# untitled.net
KiCad netlist of a schematic drawn in EAGLE
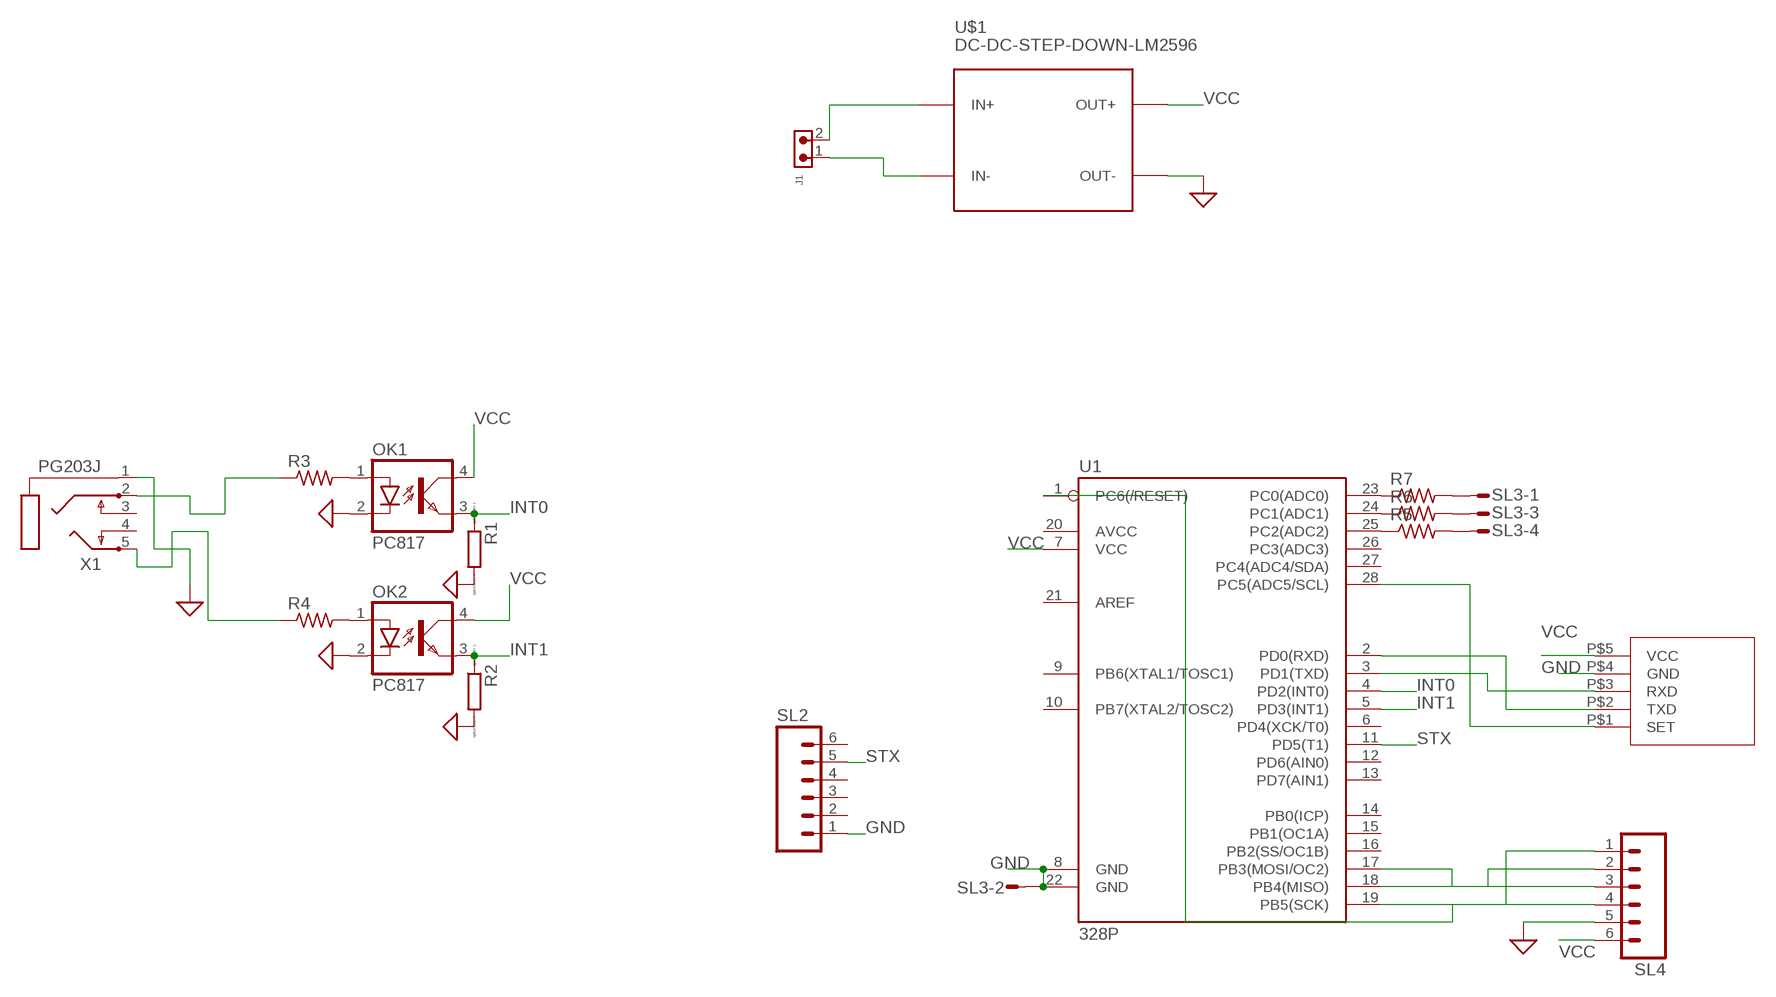
[diagram p0: schematic, sheet 1]

(export (version "E")
  (design (tool "Eeschema 10.0.6"))
  (components
    (comp (ref "J1")
      (value "691305530002")
      (footprint "eagle-import:691305530002")
      (libsource (lib "eagle-import") (part "691305530002"))
    )
    (comp (ref "OK1")
      (value "PC817")
      (footprint "eagle-import:DIL04")
      (fields (field (name "MPN") "PC817X4J000F"))
      (libsource (lib "eagle-import") (part "PC817"))
    )
    (comp (ref "OK2")
      (value "PC817")
      (footprint "eagle-import:DIL04")
      (fields (field (name "MPN") "PC817X4J000F"))
      (libsource (lib "eagle-import") (part "PC817"))
    )
    (comp (ref "R1")
      (value "R0207/10")
      (footprint "eagle-import:0207_10")
      (libsource (lib "eagle-import") (part "R0207/10"))
    )
    (comp (ref "R2")
      (value "R0207/10")
      (footprint "eagle-import:0207_10")
      (libsource (lib "eagle-import") (part "R0207/10"))
    )
    (comp (ref "R3")
      (value "R-US_0207/10")
      (footprint "eagle-import:0207_10")
      (libsource (lib "eagle-import") (part "R-US_0207/10"))
    )
    (comp (ref "R4")
      (value "R-US_0207/10")
      (footprint "eagle-import:0207_10")
      (libsource (lib "eagle-import") (part "R-US_0207/10"))
    )
    (comp (ref "R5")
      (value "R-US_0204/2V")
      (footprint "eagle-import:0204V")
      (libsource (lib "eagle-import") (part "R-US_0204/2V"))
    )
    (comp (ref "R6")
      (value "R-US_0204/2V")
      (footprint "eagle-import:0204V")
      (libsource (lib "eagle-import") (part "R-US_0204/2V"))
    )
    (comp (ref "R7")
      (value "R-US_0207/7")
      (footprint "eagle-import:0207_7")
      (libsource (lib "eagle-import") (part "R-US_0207/7"))
    )
    (comp (ref "SL2")
      (value "M06")
      (footprint "eagle-import:06P")
      (libsource (lib "eagle-import") (part "M06"))
    )
    (comp (ref "SL3")
      (value "M04S")
      (footprint "eagle-import:04P")
      (libsource (lib "eagle-import") (part "M04S"))
    )
    (comp (ref "SL4")
      (value "M06")
      (footprint "eagle-import:06P")
      (libsource (lib "eagle-import") (part "M06"))
    )
    (comp (ref "U$1")
      (value "DC-DC-STEP-DOWN-LM2596")
      (footprint "eagle-import:DC-DC-STEP-DOWN-LM2596")
      (libsource (lib "eagle-import") (part "DC-DC-STEP-DOWN-LM2596"))
    )
    (comp (ref "U$3")
      (value "HC12")
      (footprint "eagle-import:HC12")
      (libsource (lib "eagle-import") (part "HC12"))
    )
    (comp (ref "U1")
      (value "328P")
      (footprint "eagle-import:DIP28")
      (libsource (lib "eagle-import") (part "ATMEGA328P_PDIP"))
    )
    (comp (ref "X1")
      (value "PG203J")
      (footprint "eagle-import:PG203J")
      (libsource (lib "eagle-import") (part "PG203J"))
    )
  )
  (nets
    (net (code "1") (name "/INT0") (class "Default")
      (node (ref "OK1") (pin "3") (pinfunction "EMIT_3") (pintype "passive"))
      (node (ref "R1") (pin "1") (pinfunction "1_1") (pintype "passive"))
      (node (ref "U1") (pin "4") (pinfunction "PD2(INT0)_4") (pintype "bidirectional"))
    )
    (net (code "2") (name "/INT1") (class "Default")
      (node (ref "OK2") (pin "3") (pinfunction "EMIT_3") (pintype "passive"))
      (node (ref "R2") (pin "1") (pinfunction "1_1") (pintype "passive"))
      (node (ref "U1") (pin "5") (pinfunction "PD3(INT1)_5") (pintype "bidirectional"))
    )
    (net (code "3") (name "/STX") (class "Default")
      (node (ref "SL2") (pin "5") (pinfunction "5_5") (pintype "passive"))
      (node (ref "U1") (pin "11") (pinfunction "PD5(T1)_11") (pintype "bidirectional"))
    )
    (net (code "4") (name "/VCC") (class "Default")
      (node (ref "OK1") (pin "4") (pinfunction "COL_4") (pintype "passive"))
      (node (ref "OK2") (pin "4") (pinfunction "COL_4") (pintype "passive"))
      (node (ref "SL4") (pin "6") (pinfunction "6_6") (pintype "passive"))
      (node (ref "U$1") (pin "OUT+") (pinfunction "OUT+_OUT+") (pintype "bidirectional"))
      (node (ref "U$3") (pin "P$5") (pinfunction "VCC_P$5") (pintype "bidirectional"))
      (node (ref "U1") (pin "7") (pinfunction "VCC_7") (pintype "bidirectional"))
    )
    (net (code "5") (name "Net-(J1-Pad1)") (class "Default")
      (node (ref "J1") (pin "1") (pinfunction "1_1") (pintype "passive"))
      (node (ref "U$1") (pin "IN-") (pinfunction "IN-_IN-") (pintype "bidirectional"))
    )
    (net (code "6") (name "Net-(J1-Pad2)") (class "Default")
      (node (ref "J1") (pin "2") (pinfunction "2_2") (pintype "passive"))
      (node (ref "U$1") (pin "IN+") (pinfunction "IN+_IN+") (pintype "bidirectional"))
    )
    (net (code "7") (name "Net-(OK1-A)") (class "Default")
      (node (ref "OK1") (pin "1") (pinfunction "A_1") (pintype "passive"))
      (node (ref "R3") (pin "2") (pinfunction "2_2") (pintype "passive"))
    )
    (net (code "8") (name "Net-(OK2-A)") (class "Default")
      (node (ref "OK2") (pin "1") (pinfunction "A_1") (pintype "passive"))
      (node (ref "R4") (pin "2") (pinfunction "2_2") (pintype "passive"))
    )
    (net (code "9") (name "Net-(R3-Pad1)") (class "Default")
      (node (ref "R3") (pin "1") (pinfunction "1_1") (pintype "passive"))
      (node (ref "X1") (pin "2") (pinfunction "2_2") (pintype "passive"))
    )
    (net (code "10") (name "Net-(R4-Pad1)") (class "Default")
      (node (ref "R4") (pin "1") (pinfunction "1_1") (pintype "passive"))
      (node (ref "X1") (pin "5") (pinfunction "5_5") (pintype "passive"))
    )
    (net (code "11") (name "Net-(SL3A-S)") (class "Default")
      (node (ref "R7") (pin "2") (pinfunction "2_2") (pintype "passive"))
      (node (ref "SL3") (pin "1") (pinfunction "S_1") (pintype "passive"))
    )
    (net (code "12") (name "Net-(SL3C-S)") (class "Default")
      (node (ref "R6") (pin "2") (pinfunction "2_2") (pintype "passive"))
      (node (ref "SL3") (pin "3") (pinfunction "S_3") (pintype "passive"))
    )
    (net (code "13") (name "Net-(SL3D-S)") (class "Default")
      (node (ref "R5") (pin "2") (pinfunction "2_2") (pintype "passive"))
      (node (ref "SL3") (pin "4") (pinfunction "S_4") (pintype "passive"))
    )
    (net (code "14") (name "Net-(U$3-RXD)") (class "Default")
      (node (ref "U$3") (pin "P$3") (pinfunction "RXD_P$3") (pintype "bidirectional"))
      (node (ref "U1") (pin "3") (pinfunction "PD1(TXD)_3") (pintype "bidirectional"))
    )
    (net (code "15") (name "Net-(U$3-SET)") (class "Default")
      (node (ref "U$3") (pin "P$1") (pinfunction "SET_P$1") (pintype "bidirectional"))
      (node (ref "U1") (pin "28") (pinfunction "PC5(ADC5/SCL)_28") (pintype "bidirectional"))
    )
    (net (code "16") (name "Net-(U$3-TXD)") (class "Default")
      (node (ref "U$3") (pin "P$2") (pinfunction "TXD_P$2") (pintype "bidirectional"))
      (node (ref "U1") (pin "2") (pinfunction "PD0(RXD)_2") (pintype "bidirectional"))
    )
    (net (code "17") (name "Net-(U1-PB3(MOSI{slash}OC2))") (class "Default")
      (node (ref "SL4") (pin "3") (pinfunction "3_3") (pintype "passive"))
      (node (ref "U1") (pin "17") (pinfunction "PB3(MOSI/OC2)_17") (pintype "bidirectional"))
    )
    (net (code "18") (name "Net-(U1-PB4(MISO))") (class "Default")
      (node (ref "SL4") (pin "2") (pinfunction "2_2") (pintype "passive"))
      (node (ref "U1") (pin "18") (pinfunction "PB4(MISO)_18") (pintype "bidirectional"))
    )
    (net (code "19") (name "Net-(U1-PB5(SCK))") (class "Default")
      (node (ref "SL4") (pin "1") (pinfunction "1_1") (pintype "passive"))
      (node (ref "U1") (pin "19") (pinfunction "PB5(SCK)_19") (pintype "bidirectional"))
    )
    (net (code "20") (name "Net-(U1-PC0(ADC0))") (class "Default")
      (node (ref "R7") (pin "1") (pinfunction "1_1") (pintype "passive"))
      (node (ref "U1") (pin "23") (pinfunction "PC0(ADC0)_23") (pintype "bidirectional"))
    )
    (net (code "21") (name "Net-(U1-PC1(ADC1))") (class "Default")
      (node (ref "R6") (pin "1") (pinfunction "1_1") (pintype "passive"))
      (node (ref "U1") (pin "24") (pinfunction "PC1(ADC1)_24") (pintype "bidirectional"))
    )
    (net (code "22") (name "Net-(U1-PC2(ADC2))") (class "Default")
      (node (ref "R5") (pin "1") (pinfunction "1_1") (pintype "passive"))
      (node (ref "U1") (pin "25") (pinfunction "PC2(ADC2)_25") (pintype "bidirectional"))
    )
    (net (code "23") (name "Net-(U1-PC6({slash}RESET))") (class "Default")
      (node (ref "SL4") (pin "4") (pinfunction "4_4") (pintype "passive"))
      (node (ref "U1") (pin "1") (pinfunction "PC6(/RESET)_1") (pintype "bidirectional"))
    )
    (net (code "24") (name "SUP") (class "Default")
      (node (ref "OK1") (pin "2") (pinfunction "C_2") (pintype "passive"))
      (node (ref "OK2") (pin "2") (pinfunction "C_2") (pintype "passive"))
      (node (ref "R1") (pin "2") (pinfunction "2_2") (pintype "passive"))
      (node (ref "R2") (pin "2") (pinfunction "2_2") (pintype "passive"))
      (node (ref "SL2") (pin "1") (pinfunction "1_1") (pintype "passive"))
      (node (ref "SL3") (pin "2") (pinfunction "S_2") (pintype "passive"))
      (node (ref "SL4") (pin "5") (pinfunction "5_5") (pintype "passive"))
      (node (ref "U$1") (pin "OUT-") (pinfunction "OUT-_OUT-") (pintype "bidirectional"))
      (node (ref "U$3") (pin "P$4") (pinfunction "GND_P$4") (pintype "bidirectional"))
      (node (ref "U1") (pin "22") (pinfunction "GND_22") (pintype "bidirectional"))
      (node (ref "U1") (pin "8") (pinfunction "GND_8") (pintype "bidirectional"))
      (node (ref "X1") (pin "1") (pinfunction "1_1") (pintype "passive"))
    )
    (net (code "25") (name "unconnected-(SL2-Pad2)") (class "Default")
      (node (ref "SL2") (pin "2") (pinfunction "2_2") (pintype "passive"))
    )
    (net (code "26") (name "unconnected-(SL2-Pad3)") (class "Default")
      (node (ref "SL2") (pin "3") (pinfunction "3_3") (pintype "passive"))
    )
    (net (code "27") (name "unconnected-(SL2-Pad4)") (class "Default")
      (node (ref "SL2") (pin "4") (pinfunction "4_4") (pintype "passive"))
    )
    (net (code "28") (name "unconnected-(SL2-Pad6)") (class "Default")
      (node (ref "SL2") (pin "6") (pinfunction "6_6") (pintype "passive"))
    )
    (net (code "29") (name "unconnected-(U1-AREF-Pad21)") (class "Default")
      (node (ref "U1") (pin "21") (pinfunction "AREF_21") (pintype "bidirectional"))
    )
    (net (code "30") (name "unconnected-(U1-AVCC-Pad20)") (class "Default")
      (node (ref "U1") (pin "20") (pinfunction "AVCC_20") (pintype "bidirectional"))
    )
    (net (code "31") (name "unconnected-(U1-PB0(ICP)-Pad14)") (class "Default")
      (node (ref "U1") (pin "14") (pinfunction "PB0(ICP)_14") (pintype "bidirectional"))
    )
    (net (code "32") (name "unconnected-(U1-PB1(OC1A)-Pad15)") (class "Default")
      (node (ref "U1") (pin "15") (pinfunction "PB1(OC1A)_15") (pintype "bidirectional"))
    )
    (net (code "33") (name "unconnected-(U1-PB2(SS{slash}OC1B)-Pad16)") (class "Default")
      (node (ref "U1") (pin "16") (pinfunction "PB2(SS/OC1B)_16") (pintype "bidirectional"))
    )
    (net (code "34") (name "unconnected-(U1-PB6(XTAL1{slash}TOSC1)-Pad9)") (class "Default")
      (node (ref "U1") (pin "9") (pinfunction "PB6(XTAL1/TOSC1)_9") (pintype "bidirectional"))
    )
    (net (code "35") (name "unconnected-(U1-PB7(XTAL2{slash}TOSC2)-Pad10)") (class "Default")
      (node (ref "U1") (pin "10") (pinfunction "PB7(XTAL2/TOSC2)_10") (pintype "bidirectional"))
    )
    (net (code "36") (name "unconnected-(U1-PC3(ADC3)-Pad26)") (class "Default")
      (node (ref "U1") (pin "26") (pinfunction "PC3(ADC3)_26") (pintype "bidirectional"))
    )
    (net (code "37") (name "unconnected-(U1-PC4(ADC4{slash}SDA)-Pad27)") (class "Default")
      (node (ref "U1") (pin "27") (pinfunction "PC4(ADC4/SDA)_27") (pintype "bidirectional"))
    )
    (net (code "38") (name "unconnected-(U1-PD4(XCK{slash}T0)-Pad6)") (class "Default")
      (node (ref "U1") (pin "6") (pinfunction "PD4(XCK/T0)_6") (pintype "bidirectional"))
    )
    (net (code "39") (name "unconnected-(U1-PD6(AIN0)-Pad12)") (class "Default")
      (node (ref "U1") (pin "12") (pinfunction "PD6(AIN0)_12") (pintype "bidirectional"))
    )
    (net (code "40") (name "unconnected-(U1-PD7(AIN1)-Pad13)") (class "Default")
      (node (ref "U1") (pin "13") (pinfunction "PD7(AIN1)_13") (pintype "bidirectional"))
    )
    (net (code "41") (name "unconnected-(X1-Pad3)") (class "Default")
      (node (ref "X1") (pin "3") (pinfunction "3_3") (pintype "passive"))
    )
    (net (code "42") (name "unconnected-(X1-Pad4)") (class "Default")
      (node (ref "X1") (pin "4") (pinfunction "4_4") (pintype "passive"))
    )
  )
)
